# PCB_Sensor_Sentuh_kapasitif_6.net
KiCad netlist of a schematic drawn in Altium Designer
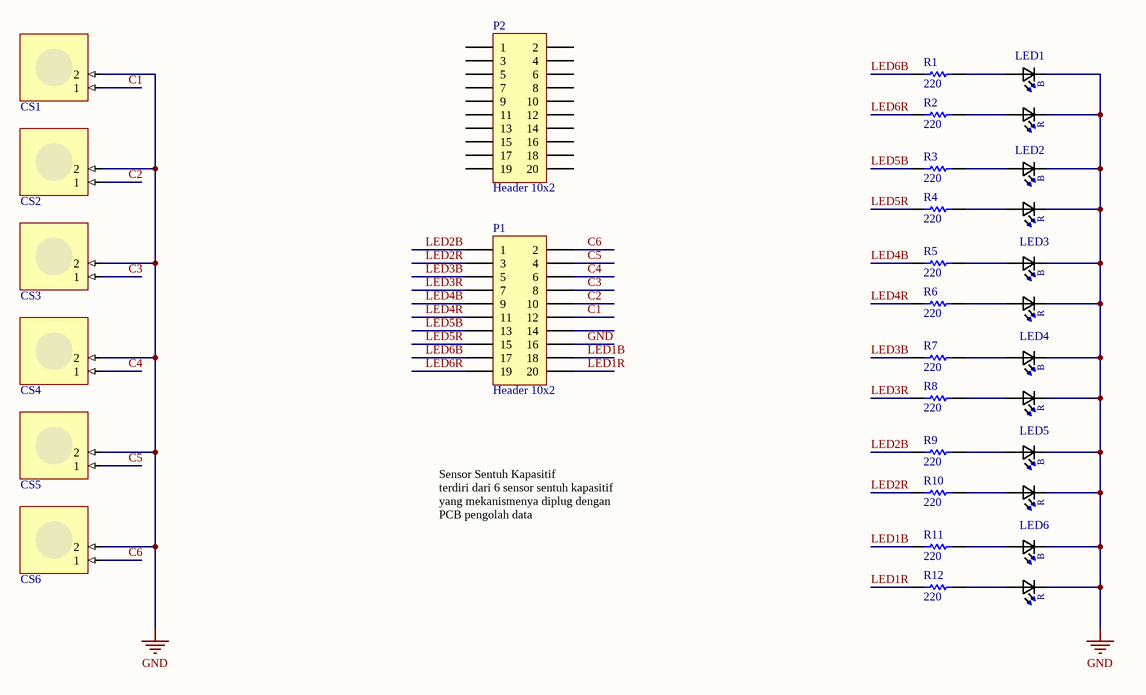
[diagram p0: PCB Sensor Sentuh kapasitif 6.SchDoc]

(export (version "E")
  (design (tool "Eeschema 10.0.6"))
  (components
    (comp (ref "CS1")
      (value "Mutual Ring mTouch Sensor")
      (libsource (lib "Microchip mTouch") (part "mTouchMutualRingSensor"))
    )
    (comp (ref "CS2")
      (value "Mutual Ring mTouch Sensor")
      (libsource (lib "Microchip mTouch") (part "mTouchMutualRingSensor"))
    )
    (comp (ref "CS3")
      (value "Mutual Ring mTouch Sensor")
      (libsource (lib "Microchip mTouch") (part "mTouchMutualRingSensor"))
    )
    (comp (ref "CS4")
      (value "Mutual Ring mTouch Sensor")
      (libsource (lib "Microchip mTouch") (part "mTouchMutualRingSensor"))
    )
    (comp (ref "CS5")
      (value "Mutual Ring mTouch Sensor")
      (libsource (lib "Microchip mTouch") (part "mTouchMutualRingSensor"))
    )
    (comp (ref "CS6")
      (value "Mutual Ring mTouch Sensor")
      (libsource (lib "Microchip mTouch") (part "mTouchMutualRingSensor"))
    )
    (comp (ref "LED1")
      (value "LTST-C195KGJRKT")
      (footprint "LTST-BILED-15X16_LTST-C195KGJRKT(HOLE)")
      (description "Green/Red 130%C2%B0 Water Clear 35/25 mcd 2 V 0605 Surface Mount Bi-Color LED")
      (fields (field (name "MF") "Lite-On"))
      (libsource (lib "REDBLUE") (part "LTST-C195KGJRKT"))
    )
    (comp (ref "LED2")
      (value "LTST-C195KGJRKT")
      (footprint "LTST-BILED-15X16_LTST-C195KGJRKT(HOLE)")
      (description "Green/Red 130%C2%B0 Water Clear 35/25 mcd 2 V 0605 Surface Mount Bi-Color LED")
      (fields (field (name "MF") "Lite-On"))
      (libsource (lib "REDBLUE") (part "LTST-C195KGJRKT"))
    )
    (comp (ref "LED3")
      (value "LTST-C195KGJRKT")
      (footprint "LTST-BILED-15X16_LTST-C195KGJRKT(HOLE)")
      (description "Green/Red 130%C2%B0 Water Clear 35/25 mcd 2 V 0605 Surface Mount Bi-Color LED")
      (fields (field (name "MF") "Lite-On"))
      (libsource (lib "REDBLUE") (part "LTST-C195KGJRKT"))
    )
    (comp (ref "LED4")
      (value "LTST-C195KGJRKT")
      (footprint "LTST-BILED-15X16_LTST-C195KGJRKT(HOLE)")
      (description "Green/Red 130%C2%B0 Water Clear 35/25 mcd 2 V 0605 Surface Mount Bi-Color LED")
      (fields (field (name "MF") "Lite-On"))
      (libsource (lib "REDBLUE") (part "LTST-C195KGJRKT"))
    )
    (comp (ref "LED5")
      (value "LTST-C195KGJRKT")
      (footprint "LTST-BILED-15X16_LTST-C195KGJRKT(HOLE)")
      (description "Green/Red 130%C2%B0 Water Clear 35/25 mcd 2 V 0605 Surface Mount Bi-Color LED")
      (fields (field (name "MF") "Lite-On"))
      (libsource (lib "REDBLUE") (part "LTST-C195KGJRKT"))
    )
    (comp (ref "LED6")
      (value "LTST-C195KGJRKT")
      (footprint "LTST-BILED-15X16_LTST-C195KGJRKT(Primary)")
      (description "Green/Red 130%C2%B0 Water Clear 35/25 mcd 2 V 0605 Surface Mount Bi-Color LED")
      (fields (field (name "MF") "Lite-On"))
      (libsource (lib "REDBLUE") (part "LTST-C195KGJRKT"))
    )
    (comp (ref "P1")
      (value "Header 10x2")
      (footprint "HDR2X10 pitch 2mm male")
      (description "Header, 14-Pin, Dual row")
      (fields (field (name "PUBLISHER") "Altium Limited"))
      (libsource (lib "RMPLib") (part "Header 10x2"))
    )
    (comp (ref "P2")
      (value "Header 10x2")
      (footprint "HDR2X10 pitch 2mm male")
      (description "Header, 14-Pin, Dual row")
      (fields (field (name "PUBLISHER") "Altium Limited"))
      (libsource (lib "RMPLib") (part "Header 10x2"))
    )
    (comp (ref "R1")
      (value "220")
      (footprint "RESC1608M")
      (description "Resistor")
      (fields (field (name "Comment") "Res1") (field (name "PUBLISHER") "Altium Limited"))
      (libsource (lib "Miscellaneous Devices") (part "Res1"))
    )
    (comp (ref "R2")
      (value "220")
      (footprint "RESC1608M")
      (description "Resistor")
      (fields (field (name "Comment") "Res1") (field (name "PUBLISHER") "Altium Limited"))
      (libsource (lib "Miscellaneous Devices") (part "Res1"))
    )
    (comp (ref "R3")
      (value "220")
      (footprint "RESC1608M")
      (description "Resistor")
      (fields (field (name "Comment") "Res1") (field (name "PUBLISHER") "Altium Limited"))
      (libsource (lib "Miscellaneous Devices") (part "Res1"))
    )
    (comp (ref "R4")
      (value "220")
      (footprint "RESC1608M")
      (description "Resistor")
      (fields (field (name "Comment") "Res1") (field (name "PUBLISHER") "Altium Limited"))
      (libsource (lib "Miscellaneous Devices") (part "Res1"))
    )
    (comp (ref "R5")
      (value "220")
      (footprint "RESC1608M")
      (description "Resistor")
      (fields (field (name "Comment") "Res1") (field (name "PUBLISHER") "Altium Limited"))
      (libsource (lib "Miscellaneous Devices") (part "Res1"))
    )
    (comp (ref "R6")
      (value "220")
      (footprint "RESC1608M")
      (description "Resistor")
      (fields (field (name "Comment") "Res1") (field (name "PUBLISHER") "Altium Limited"))
      (libsource (lib "Miscellaneous Devices") (part "Res1"))
    )
    (comp (ref "R7")
      (value "220")
      (footprint "RESC1608M")
      (description "Resistor")
      (fields (field (name "Comment") "Res1") (field (name "PUBLISHER") "Altium Limited"))
      (libsource (lib "Miscellaneous Devices") (part "Res1"))
    )
    (comp (ref "R8")
      (value "220")
      (footprint "RESC1608M")
      (description "Resistor")
      (fields (field (name "Comment") "Res1") (field (name "PUBLISHER") "Altium Limited"))
      (libsource (lib "Miscellaneous Devices") (part "Res1"))
    )
    (comp (ref "R9")
      (value "220")
      (footprint "RESC1608M")
      (description "Resistor")
      (fields (field (name "Comment") "Res1") (field (name "PUBLISHER") "Altium Limited"))
      (libsource (lib "Miscellaneous Devices") (part "Res1"))
    )
    (comp (ref "R10")
      (value "220")
      (footprint "RESC1608M")
      (description "Resistor")
      (fields (field (name "Comment") "Res1") (field (name "PUBLISHER") "Altium Limited"))
      (libsource (lib "Miscellaneous Devices") (part "Res1"))
    )
    (comp (ref "R11")
      (value "220")
      (footprint "RESC1608M")
      (description "Resistor")
      (fields (field (name "Comment") "Res1") (field (name "PUBLISHER") "Altium Limited"))
      (libsource (lib "Miscellaneous Devices") (part "Res1"))
    )
    (comp (ref "R12")
      (value "220")
      (footprint "RESC1608M")
      (description "Resistor")
      (fields (field (name "Comment") "Res1") (field (name "PUBLISHER") "Altium Limited"))
      (libsource (lib "Miscellaneous Devices") (part "Res1"))
    )
  )
  (nets
    (net (code "1") (name "/C1") (class "Default")
      (node (ref "CS1") (pin "1") (pinfunction "1_1") (pintype "input"))
      (node (ref "P1") (pin "12") (pinfunction "12_12") (pintype "passive"))
    )
    (net (code "2") (name "/C2") (class "Default")
      (node (ref "CS2") (pin "1") (pinfunction "1_1") (pintype "input"))
      (node (ref "P1") (pin "10") (pinfunction "10_10") (pintype "passive"))
    )
    (net (code "3") (name "/C3") (class "Default")
      (node (ref "CS3") (pin "1") (pinfunction "1_1") (pintype "input"))
      (node (ref "P1") (pin "8") (pinfunction "8_8") (pintype "passive"))
    )
    (net (code "4") (name "/C4") (class "Default")
      (node (ref "CS4") (pin "1") (pinfunction "1_1") (pintype "input"))
      (node (ref "P1") (pin "6") (pinfunction "6_6") (pintype "passive"))
    )
    (net (code "5") (name "/C5") (class "Default")
      (node (ref "CS5") (pin "1") (pinfunction "1_1") (pintype "input"))
      (node (ref "P1") (pin "4") (pinfunction "4_4") (pintype "passive"))
    )
    (net (code "6") (name "/C6") (class "Default")
      (node (ref "CS6") (pin "1") (pinfunction "1_1") (pintype "input"))
      (node (ref "P1") (pin "2") (pinfunction "2_2") (pintype "passive"))
    )
    (net (code "7") (name "/LED1B") (class "Default")
      (node (ref "P1") (pin "18") (pinfunction "18_18") (pintype "passive"))
      (node (ref "R11") (pin "1") (pinfunction "1_1") (pintype "passive"))
    )
    (net (code "8") (name "/LED1R") (class "Default")
      (node (ref "P1") (pin "20") (pinfunction "20_20") (pintype "passive"))
      (node (ref "R12") (pin "1") (pinfunction "1_1") (pintype "passive"))
    )
    (net (code "9") (name "/LED2B") (class "Default")
      (node (ref "P1") (pin "1") (pinfunction "1_1") (pintype "passive"))
      (node (ref "R9") (pin "1") (pinfunction "1_1") (pintype "passive"))
    )
    (net (code "10") (name "/LED2R") (class "Default")
      (node (ref "P1") (pin "3") (pinfunction "3_3") (pintype "passive"))
      (node (ref "R10") (pin "1") (pinfunction "1_1") (pintype "passive"))
    )
    (net (code "11") (name "/LED3B") (class "Default")
      (node (ref "P1") (pin "5") (pinfunction "5_5") (pintype "passive"))
      (node (ref "R7") (pin "1") (pinfunction "1_1") (pintype "passive"))
    )
    (net (code "12") (name "/LED3R") (class "Default")
      (node (ref "P1") (pin "7") (pinfunction "7_7") (pintype "passive"))
      (node (ref "R8") (pin "1") (pinfunction "1_1") (pintype "passive"))
    )
    (net (code "13") (name "/LED4B") (class "Default")
      (node (ref "P1") (pin "9") (pinfunction "9_9") (pintype "passive"))
      (node (ref "R5") (pin "1") (pinfunction "1_1") (pintype "passive"))
    )
    (net (code "14") (name "/LED4R") (class "Default")
      (node (ref "P1") (pin "11") (pinfunction "11_11") (pintype "passive"))
      (node (ref "R6") (pin "1") (pinfunction "1_1") (pintype "passive"))
    )
    (net (code "15") (name "/LED5B") (class "Default")
      (node (ref "P1") (pin "13") (pinfunction "13_13") (pintype "passive"))
      (node (ref "R3") (pin "1") (pinfunction "1_1") (pintype "passive"))
    )
    (net (code "16") (name "/LED5R") (class "Default")
      (node (ref "P1") (pin "15") (pinfunction "15_15") (pintype "passive"))
      (node (ref "R4") (pin "1") (pinfunction "1_1") (pintype "passive"))
    )
    (net (code "17") (name "/LED6B") (class "Default")
      (node (ref "P1") (pin "17") (pinfunction "17_17") (pintype "passive"))
      (node (ref "R1") (pin "1") (pinfunction "1_1") (pintype "passive"))
    )
    (net (code "18") (name "/LED6R") (class "Default")
      (node (ref "P1") (pin "19") (pinfunction "19_19") (pintype "passive"))
      (node (ref "R2") (pin "1") (pinfunction "1_1") (pintype "passive"))
    )
    (net (code "19") (name "GND") (class "Default")
      (node (ref "CS1") (pin "2") (pinfunction "2_2") (pintype "input"))
      (node (ref "CS2") (pin "2") (pinfunction "2_2") (pintype "input"))
      (node (ref "CS3") (pin "2") (pinfunction "2_2") (pintype "input"))
      (node (ref "CS4") (pin "2") (pinfunction "2_2") (pintype "input"))
      (node (ref "CS5") (pin "2") (pinfunction "2_2") (pintype "input"))
      (node (ref "CS6") (pin "2") (pinfunction "2_2") (pintype "input"))
      (node (ref "LED1") (pin "P$3") (pinfunction "K1_P$3") (pintype "passive"))
      (node (ref "LED1") (pin "P$4") (pinfunction "K2_P$4") (pintype "passive"))
      (node (ref "LED2") (pin "P$3") (pinfunction "K1_P$3") (pintype "passive"))
      (node (ref "LED2") (pin "P$4") (pinfunction "K2_P$4") (pintype "passive"))
      (node (ref "LED3") (pin "P$3") (pinfunction "K1_P$3") (pintype "passive"))
      (node (ref "LED3") (pin "P$4") (pinfunction "K2_P$4") (pintype "passive"))
      (node (ref "LED4") (pin "P$3") (pinfunction "K1_P$3") (pintype "passive"))
      (node (ref "LED4") (pin "P$4") (pinfunction "K2_P$4") (pintype "passive"))
      (node (ref "LED5") (pin "P$3") (pinfunction "K1_P$3") (pintype "passive"))
      (node (ref "LED5") (pin "P$4") (pinfunction "K2_P$4") (pintype "passive"))
      (node (ref "LED6") (pin "P$3") (pinfunction "K1_P$3") (pintype "passive"))
      (node (ref "LED6") (pin "P$4") (pinfunction "K2_P$4") (pintype "passive"))
      (node (ref "P1") (pin "16") (pinfunction "16_16") (pintype "passive"))
    )
    (net (code "20") (name "Net-(LED1-A1)") (class "Default")
      (node (ref "LED1") (pin "P$1") (pinfunction "A1_P$1") (pintype "passive"))
      (node (ref "R1") (pin "2") (pinfunction "2_2") (pintype "passive"))
    )
    (net (code "21") (name "Net-(LED1-A2)") (class "Default")
      (node (ref "LED1") (pin "P$2") (pinfunction "A2_P$2") (pintype "passive"))
      (node (ref "R2") (pin "2") (pinfunction "2_2") (pintype "passive"))
    )
    (net (code "22") (name "Net-(LED2-A1)") (class "Default")
      (node (ref "LED2") (pin "P$1") (pinfunction "A1_P$1") (pintype "passive"))
      (node (ref "R3") (pin "2") (pinfunction "2_2") (pintype "passive"))
    )
    (net (code "23") (name "Net-(LED2-A2)") (class "Default")
      (node (ref "LED2") (pin "P$2") (pinfunction "A2_P$2") (pintype "passive"))
      (node (ref "R4") (pin "2") (pinfunction "2_2") (pintype "passive"))
    )
    (net (code "24") (name "Net-(LED3-A1)") (class "Default")
      (node (ref "LED3") (pin "P$1") (pinfunction "A1_P$1") (pintype "passive"))
      (node (ref "R5") (pin "2") (pinfunction "2_2") (pintype "passive"))
    )
    (net (code "25") (name "Net-(LED3-A2)") (class "Default")
      (node (ref "LED3") (pin "P$2") (pinfunction "A2_P$2") (pintype "passive"))
      (node (ref "R6") (pin "2") (pinfunction "2_2") (pintype "passive"))
    )
    (net (code "26") (name "Net-(LED4-A1)") (class "Default")
      (node (ref "LED4") (pin "P$1") (pinfunction "A1_P$1") (pintype "passive"))
      (node (ref "R7") (pin "2") (pinfunction "2_2") (pintype "passive"))
    )
    (net (code "27") (name "Net-(LED4-A2)") (class "Default")
      (node (ref "LED4") (pin "P$2") (pinfunction "A2_P$2") (pintype "passive"))
      (node (ref "R8") (pin "2") (pinfunction "2_2") (pintype "passive"))
    )
    (net (code "28") (name "Net-(LED5-A1)") (class "Default")
      (node (ref "LED5") (pin "P$1") (pinfunction "A1_P$1") (pintype "passive"))
      (node (ref "R9") (pin "2") (pinfunction "2_2") (pintype "passive"))
    )
    (net (code "29") (name "Net-(LED5-A2)") (class "Default")
      (node (ref "LED5") (pin "P$2") (pinfunction "A2_P$2") (pintype "passive"))
      (node (ref "R10") (pin "2") (pinfunction "2_2") (pintype "passive"))
    )
    (net (code "30") (name "Net-(LED6-A1)") (class "Default")
      (node (ref "LED6") (pin "P$1") (pinfunction "A1_P$1") (pintype "passive"))
      (node (ref "R11") (pin "2") (pinfunction "2_2") (pintype "passive"))
    )
    (net (code "31") (name "Net-(LED6-A2)") (class "Default")
      (node (ref "LED6") (pin "P$2") (pinfunction "A2_P$2") (pintype "passive"))
      (node (ref "R12") (pin "2") (pinfunction "2_2") (pintype "passive"))
    )
    (net (code "32") (name "unconnected-(P1-Pad14)") (class "Default")
      (node (ref "P1") (pin "14") (pinfunction "14_14") (pintype "passive"))
    )
    (net (code "33") (name "unconnected-(P2-Pad1)") (class "Default")
      (node (ref "P2") (pin "1") (pinfunction "1_1") (pintype "passive"))
    )
    (net (code "34") (name "unconnected-(P2-Pad2)") (class "Default")
      (node (ref "P2") (pin "2") (pinfunction "2_2") (pintype "passive"))
    )
    (net (code "35") (name "unconnected-(P2-Pad3)") (class "Default")
      (node (ref "P2") (pin "3") (pinfunction "3_3") (pintype "passive"))
    )
    (net (code "36") (name "unconnected-(P2-Pad4)") (class "Default")
      (node (ref "P2") (pin "4") (pinfunction "4_4") (pintype "passive"))
    )
    (net (code "37") (name "unconnected-(P2-Pad5)") (class "Default")
      (node (ref "P2") (pin "5") (pinfunction "5_5") (pintype "passive"))
    )
    (net (code "38") (name "unconnected-(P2-Pad6)") (class "Default")
      (node (ref "P2") (pin "6") (pinfunction "6_6") (pintype "passive"))
    )
    (net (code "39") (name "unconnected-(P2-Pad7)") (class "Default")
      (node (ref "P2") (pin "7") (pinfunction "7_7") (pintype "passive"))
    )
    (net (code "40") (name "unconnected-(P2-Pad8)") (class "Default")
      (node (ref "P2") (pin "8") (pinfunction "8_8") (pintype "passive"))
    )
    (net (code "41") (name "unconnected-(P2-Pad9)") (class "Default")
      (node (ref "P2") (pin "9") (pinfunction "9_9") (pintype "passive"))
    )
    (net (code "42") (name "unconnected-(P2-Pad10)") (class "Default")
      (node (ref "P2") (pin "10") (pinfunction "10_10") (pintype "passive"))
    )
    (net (code "43") (name "unconnected-(P2-Pad11)") (class "Default")
      (node (ref "P2") (pin "11") (pinfunction "11_11") (pintype "passive"))
    )
    (net (code "44") (name "unconnected-(P2-Pad12)") (class "Default")
      (node (ref "P2") (pin "12") (pinfunction "12_12") (pintype "passive"))
    )
    (net (code "45") (name "unconnected-(P2-Pad13)") (class "Default")
      (node (ref "P2") (pin "13") (pinfunction "13_13") (pintype "passive"))
    )
    (net (code "46") (name "unconnected-(P2-Pad14)") (class "Default")
      (node (ref "P2") (pin "14") (pinfunction "14_14") (pintype "passive"))
    )
    (net (code "47") (name "unconnected-(P2-Pad15)") (class "Default")
      (node (ref "P2") (pin "15") (pinfunction "15_15") (pintype "passive"))
    )
    (net (code "48") (name "unconnected-(P2-Pad16)") (class "Default")
      (node (ref "P2") (pin "16") (pinfunction "16_16") (pintype "passive"))
    )
    (net (code "49") (name "unconnected-(P2-Pad17)") (class "Default")
      (node (ref "P2") (pin "17") (pinfunction "17_17") (pintype "passive"))
    )
    (net (code "50") (name "unconnected-(P2-Pad18)") (class "Default")
      (node (ref "P2") (pin "18") (pinfunction "18_18") (pintype "passive"))
    )
    (net (code "51") (name "unconnected-(P2-Pad19)") (class "Default")
      (node (ref "P2") (pin "19") (pinfunction "19_19") (pintype "passive"))
    )
    (net (code "52") (name "unconnected-(P2-Pad20)") (class "Default")
      (node (ref "P2") (pin "20") (pinfunction "20_20") (pintype "passive"))
    )
  )
)
